# Sheet.net
KiCad netlist of a schematic drawn in Altium Designer
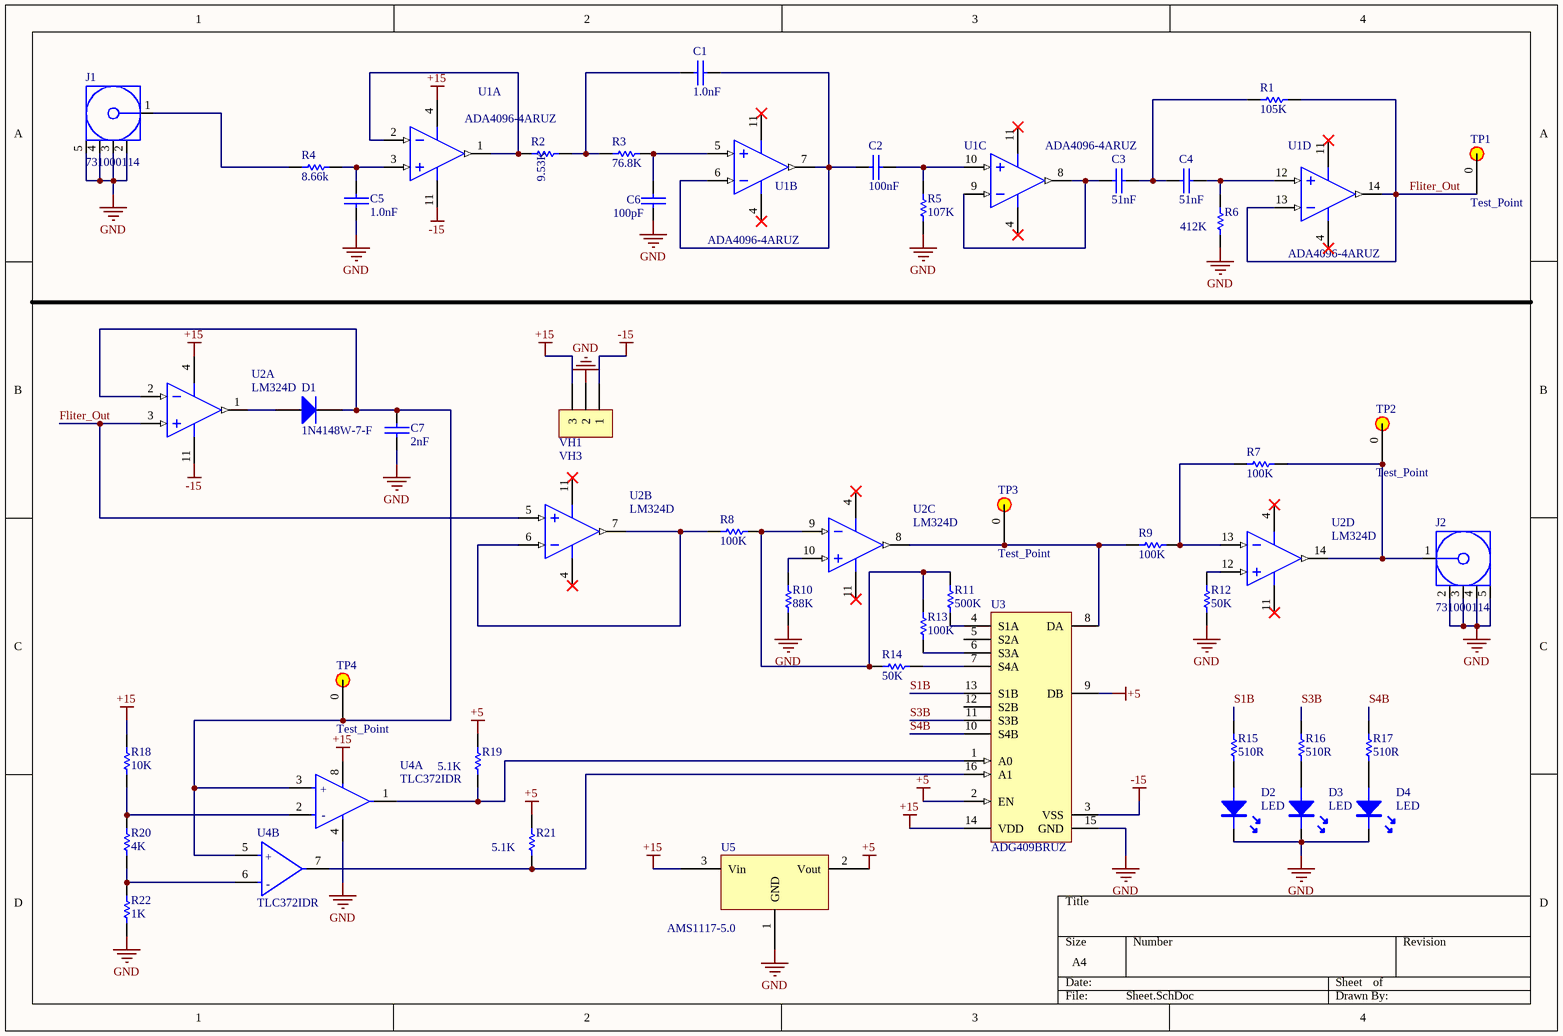
[diagram p0: Sheet.SchDoc]

(export (version "E")
  (design (tool "Eeschema 10.0.6"))
  (components
    (comp (ref "C1")
      (value "1.0nF")
      (footprint "0805C")
      (description "无极性电容")
      (libsource (lib "电容") (part "CAP"))
    )
    (comp (ref "C2")
      (value "100nF")
      (footprint "0805C")
      (description "无极性电容")
      (libsource (lib "电容") (part "CAP"))
    )
    (comp (ref "C3")
      (value "51nF")
      (footprint "0805C")
      (description "无极性电容")
      (libsource (lib "电容") (part "CAP"))
    )
    (comp (ref "C4")
      (value "51nF")
      (footprint "0805C")
      (description "无极性电容")
      (libsource (lib "电容") (part "CAP"))
    )
    (comp (ref "C5")
      (value "1.0nF")
      (footprint "0805C")
      (description "无极性电容")
      (libsource (lib "电容") (part "CAP"))
    )
    (comp (ref "C6")
      (value "100pF")
      (footprint "0805C")
      (description "无极性电容")
      (libsource (lib "电容") (part "CAP"))
    )
    (comp (ref "C7")
      (value "2nF")
      (footprint "0805C")
      (description "无极性电容")
      (libsource (lib "电容") (part "CAP"))
    )
    (comp (ref "D1")
      (value "1N4148W-7-F")
      (footprint "DIOD-SOD123-2_V")
      (description "Fast Switching Diode, 100 V, 0.15 A, -65 to 150 degC, 2-Pin?SOD123, RoHS, Tape and Reel")
      (fields (field (name "MANUFACTURER") "DiodesIncorporated"))
      (libsource (lib "Altium Content Vault") (part "D-AK-2"))
    )
    (comp (ref "D2") (value "LED") (footprint "LED-0805R") (libsource (lib "LED") (part "LED")))
    (comp (ref "D3") (value "LED") (footprint "LED-0805R") (libsource (lib "LED") (part "LED")))
    (comp (ref "D4") (value "LED") (footprint "LED-0805R") (libsource (lib "LED") (part "LED")))
    (comp (ref "J1")
      (value "731000114")
      (footprint "MOLX-731000114_V")
      (description "SMA Right-Angle PCB Jack Receptacle, Brass Body, Gold Plated, 50 Ohm, 5-Pin THD, RoHS, Tray")
      (fields (field (name "MANUFACTURER") "Molex"))
      (libsource (lib "Altium Content Vault") (part "CN-S-4F-RF5"))
    )
    (comp (ref "J2")
      (value "731000114")
      (footprint "MOLX-731000114_V")
      (description "SMA Right-Angle PCB Jack Receptacle, Brass Body, Gold Plated, 50 Ohm, 5-Pin THD, RoHS, Tray")
      (fields (field (name "MANUFACTURER") "Molex"))
      (libsource (lib "Altium Content Vault") (part "CN-S-4F-RF5"))
    )
    (comp (ref "R1") (value "105K") (footprint "0805R") (libsource (lib "电阻") (part "RES")))
    (comp (ref "R2") (value "9.53K") (footprint "0805R") (libsource (lib "电阻") (part "RES")))
    (comp (ref "R3") (value "76.8K") (footprint "0805R") (libsource (lib "电阻") (part "RES")))
    (comp (ref "R4") (value "8.66k") (footprint "0805R") (libsource (lib "电阻") (part "RES")))
    (comp (ref "R5") (value "107K") (footprint "0805R") (libsource (lib "电阻") (part "RES")))
    (comp (ref "R6") (value "412K") (footprint "0805R") (libsource (lib "电阻") (part "RES")))
    (comp (ref "R7") (value "100K") (footprint "0805R") (libsource (lib "电阻") (part "RES")))
    (comp (ref "R8") (value "100K") (footprint "0805R") (libsource (lib "电阻") (part "RES")))
    (comp (ref "R9") (value "100K") (footprint "0805R") (libsource (lib "电阻") (part "RES")))
    (comp (ref "R10") (value "88K") (footprint "0805R") (libsource (lib "电阻") (part "RES")))
    (comp (ref "R11") (value "500K") (footprint "0805R") (libsource (lib "电阻") (part "RES")))
    (comp (ref "R12") (value "50K") (footprint "0805R") (libsource (lib "电阻") (part "RES")))
    (comp (ref "R13") (value "100K") (footprint "0805R") (libsource (lib "电阻") (part "RES")))
    (comp (ref "R14") (value "50K") (footprint "0805R") (libsource (lib "电阻") (part "RES")))
    (comp (ref "R15") (value "510R") (footprint "0805R") (libsource (lib "电阻") (part "RES")))
    (comp (ref "R16") (value "510R") (footprint "0805R") (libsource (lib "电阻") (part "RES")))
    (comp (ref "R17") (value "510R") (footprint "0805R") (libsource (lib "电阻") (part "RES")))
    (comp (ref "R18") (value "10K") (footprint "0805R") (libsource (lib "电阻") (part "RES")))
    (comp (ref "R19") (value "5.1K") (footprint "0805R") (libsource (lib "电阻") (part "RES")))
    (comp (ref "R20") (value "4K") (footprint "0805R") (libsource (lib "电阻") (part "RES")))
    (comp (ref "R21") (value "5.1K") (footprint "0805R") (libsource (lib "电阻") (part "RES")))
    (comp (ref "R22") (value "1K") (footprint "0805R") (libsource (lib "电阻") (part "RES")))
    (comp (ref "TP1")
      (value "Test_Point")
      (footprint "TestPoint FootPrint")
      (libsource (lib "tp") (part "Test_Point"))
    )
    (comp (ref "TP2")
      (value "Test_Point")
      (footprint "TestPoint FootPrint")
      (libsource (lib "tp") (part "Test_Point"))
    )
    (comp (ref "TP3")
      (value "Test_Point")
      (footprint "TestPoint FootPrint")
      (libsource (lib "tp") (part "Test_Point"))
    )
    (comp (ref "TP4")
      (value "Test_Point")
      (footprint "TestPoint FootPrint")
      (libsource (lib "tp") (part "Test_Point"))
    )
    (comp (ref "U1")
      (value "ADA4096-4ARUZ")
      (footprint "ADI-RU-14_L")
      (fields (field (name "MANUFACTURER") "Analog Devices") (field (name "GENERIC PART NUMBER") "ADA4096-4"))
      (libsource (lib "Analog_Devices_ADA4096_4ARUZ") (part "ADA4096-4ARUZ"))
    )
    (comp (ref "U2")
      (value "LM324D")
      (footprint "D0014A_L")
      (fields (field (name "MANUFACTURER") "Texas Instruments"))
      (libsource (lib "Altium Content Vault") (part "TI-LMX24_2902X-X14"))
    )
    (comp (ref "U3")
      (value "ADG409BRUZ")
      (footprint "ADI-RU-16_N")
      (fields (field (name "MANUFACTURER") "Analog Devices"))
      (libsource (lib "Altium Content Vault") (part "ADI-ADG409-RU-16"))
    )
    (comp (ref "U4")
      (value "TLC372IDR")
      (footprint "FP-D0008A-MFG")
      (description "IC DIFF COMP DUAL 8-SOIC")
      (fields
        (field (name "MANUFACTURER") "Texas Instruments")
        (field (name "OCTOPART") "https://octopart.com/tlc372idr-texas+instruments-841294")
      )
      (libsource (lib "Altium Content Vault") (part "c7de155b62542436dacb6ff186a4a6f"))
    )
    (comp (ref "U5")
      (value "AMS1117-5.0")
      (footprint "SOT223")
      (description "三端稳压芯片")
      (libsource (lib "电源芯片") (part "AMS1117"))
    )
    (comp (ref "VH1") (value "VH3") (footprint "VH3.96-3A") (libsource (lib "XH，VH") (part "VH3")))
  )
  (nets
    (net (code "1") (name "+5") (class "Default")
      (node (ref "R19") (pin "2") (pinfunction "2_2") (pintype "passive"))
      (node (ref "R21") (pin "2") (pinfunction "2_2") (pintype "passive"))
      (node (ref "U3") (pin "2") (pinfunction "EN_2") (pintype "input"))
      (node (ref "U3") (pin "9") (pinfunction "DB_9") (pintype "passive"))
      (node (ref "U5") (pin "2") (pinfunction "Vout_2") (pintype "passive"))
    )
    (net (code "2") (name "+15") (class "Default")
      (node (ref "R18") (pin "2") (pinfunction "2_2") (pintype "passive"))
      (node (ref "U1") (pin "4") (pinfunction "+V_4") (pintype "power_in"))
      (node (ref "U2") (pin "4") (pinfunction "VCC_4") (pintype "power_in"))
      (node (ref "U3") (pin "14") (pinfunction "VDD_14") (pintype "power_in"))
      (node (ref "U4") (pin "8") (pinfunction "VCC_8") (pintype "power_in"))
      (node (ref "U5") (pin "3") (pinfunction "Vin_3") (pintype "passive"))
      (node (ref "VH1") (pin "3") (pinfunction "3_3") (pintype "passive"))
    )
    (net (code "3") (name "-15") (class "Default")
      (node (ref "U1") (pin "11") (pinfunction "-V_11") (pintype "power_in"))
      (node (ref "U2") (pin "11") (pinfunction "GND_11") (pintype "power_in"))
      (node (ref "U3") (pin "3") (pinfunction "VSS_3") (pintype "power_in"))
      (node (ref "VH1") (pin "1") (pinfunction "1_1") (pintype "passive"))
    )
    (net (code "4") (name "/Fliter_Out") (class "Default")
      (node (ref "R1") (pin "1") (pinfunction "1_1") (pintype "passive"))
      (node (ref "TP1") (pin "0") (pintype "passive"))
      (node (ref "U1") (pin "13") (pinfunction "-IN_D_13") (pintype "input"))
      (node (ref "U1") (pin "14") (pinfunction "OUT_D_14") (pintype "output"))
      (node (ref "U2") (pin "3") (pinfunction "1IN+_3") (pintype "input"))
      (node (ref "U2") (pin "5") (pinfunction "2IN+_5") (pintype "input"))
    )
    (net (code "5") (name "/S1B") (class "Default")
      (node (ref "R15") (pin "1") (pinfunction "1_1") (pintype "passive"))
      (node (ref "U3") (pin "13") (pinfunction "S1B_13") (pintype "passive"))
    )
    (net (code "6") (name "/S3B") (class "Default")
      (node (ref "R16") (pin "1") (pinfunction "1_1") (pintype "passive"))
      (node (ref "U3") (pin "11") (pinfunction "S3B_11") (pintype "passive"))
    )
    (net (code "7") (name "/S4B") (class "Default")
      (node (ref "R17") (pin "1") (pinfunction "1_1") (pintype "passive"))
      (node (ref "U3") (pin "10") (pinfunction "S4B_10") (pintype "passive"))
    )
    (net (code "8") (name "GND") (class "Default")
      (node (ref "C5") (pin "1") (pinfunction "1_1") (pintype "passive"))
      (node (ref "C6") (pin "1") (pinfunction "1_1") (pintype "passive"))
      (node (ref "C7") (pin "2") (pinfunction "2_2") (pintype "passive"))
      (node (ref "D2") (pin "K") (pinfunction "K_K") (pintype "passive"))
      (node (ref "D3") (pin "K") (pinfunction "K_K") (pintype "passive"))
      (node (ref "D4") (pin "K") (pinfunction "K_K") (pintype "passive"))
      (node (ref "J1") (pin "2") (pinfunction "2_2") (pintype "passive"))
      (node (ref "J1") (pin "3") (pinfunction "3_3") (pintype "passive"))
      (node (ref "J1") (pin "4") (pinfunction "4_4") (pintype "passive"))
      (node (ref "J1") (pin "5") (pinfunction "5_5") (pintype "passive"))
      (node (ref "J2") (pin "2") (pinfunction "2_2") (pintype "passive"))
      (node (ref "J2") (pin "3") (pinfunction "3_3") (pintype "passive"))
      (node (ref "J2") (pin "4") (pinfunction "4_4") (pintype "passive"))
      (node (ref "J2") (pin "5") (pinfunction "5_5") (pintype "passive"))
      (node (ref "R10") (pin "2") (pinfunction "2_2") (pintype "passive"))
      (node (ref "R12") (pin "2") (pinfunction "2_2") (pintype "passive"))
      (node (ref "R22") (pin "1") (pinfunction "1_1") (pintype "passive"))
      (node (ref "R5") (pin "1") (pinfunction "1_1") (pintype "passive"))
      (node (ref "R6") (pin "1") (pinfunction "1_1") (pintype "passive"))
      (node (ref "U3") (pin "15") (pinfunction "GND_15") (pintype "power_in"))
      (node (ref "U4") (pin "4") (pinfunction "GND_4") (pintype "power_in"))
      (node (ref "U5") (pin "1") (pinfunction "GND_1") (pintype "passive"))
      (node (ref "VH1") (pin "2") (pinfunction "2_2") (pintype "passive"))
    )
    (net (code "9") (name "Net-(C1-Pad2)") (class "Default")
      (node (ref "C1") (pin "2") (pinfunction "2_2") (pintype "passive"))
      (node (ref "R2") (pin "2") (pinfunction "2_2") (pintype "passive"))
      (node (ref "R3") (pin "1") (pinfunction "1_1") (pintype "passive"))
    )
    (net (code "10") (name "Net-(C3-Pad1)") (class "Default")
      (node (ref "C3") (pin "1") (pinfunction "1_1") (pintype "passive"))
      (node (ref "C4") (pin "2") (pinfunction "2_2") (pintype "passive"))
      (node (ref "R1") (pin "2") (pinfunction "2_2") (pintype "passive"))
    )
    (net (code "11") (name "Net-(D1-A)") (class "Default")
      (node (ref "D1") (pin "1") (pinfunction "A_1") (pintype "passive"))
      (node (ref "U2") (pin "1") (pinfunction "1OUT_1") (pintype "output"))
    )
    (net (code "12") (name "Net-(D1-K)") (class "Default")
      (node (ref "C7") (pin "1") (pinfunction "1_1") (pintype "passive"))
      (node (ref "D1") (pin "2") (pinfunction "K_2") (pintype "passive"))
      (node (ref "TP4") (pin "0") (pintype "passive"))
      (node (ref "U2") (pin "2") (pinfunction "1IN-_2") (pintype "input"))
      (node (ref "U4") (pin "3") (pinfunction "1IN+_3") (pintype "tri_state"))
      (node (ref "U4") (pin "5") (pinfunction "2IN+_5") (pintype "tri_state"))
    )
    (net (code "13") (name "Net-(D2-PadA)") (class "Default")
      (node (ref "D2") (pin "A") (pinfunction "A_A") (pintype "passive"))
      (node (ref "R15") (pin "2") (pinfunction "2_2") (pintype "passive"))
    )
    (net (code "14") (name "Net-(D3-PadA)") (class "Default")
      (node (ref "D3") (pin "A") (pinfunction "A_A") (pintype "passive"))
      (node (ref "R16") (pin "2") (pinfunction "2_2") (pintype "passive"))
    )
    (net (code "15") (name "Net-(D4-PadA)") (class "Default")
      (node (ref "D4") (pin "A") (pinfunction "A_A") (pintype "passive"))
      (node (ref "R17") (pin "2") (pinfunction "2_2") (pintype "passive"))
    )
    (net (code "16") (name "Net-(J1-Pad1)") (class "Default")
      (node (ref "J1") (pin "1") (pinfunction "1_1") (pintype "passive"))
      (node (ref "R4") (pin "1") (pinfunction "1_1") (pintype "passive"))
    )
    (net (code "17") (name "Net-(U1A-+IN_A)") (class "Default")
      (node (ref "C5") (pin "2") (pinfunction "2_2") (pintype "passive"))
      (node (ref "R4") (pin "2") (pinfunction "2_2") (pintype "passive"))
      (node (ref "U1") (pin "3") (pinfunction "+IN_A_3") (pintype "input"))
    )
    (net (code "18") (name "Net-(U1A--IN_A)") (class "Default")
      (node (ref "R2") (pin "1") (pinfunction "1_1") (pintype "passive"))
      (node (ref "U1") (pin "1") (pinfunction "OUT_A_1") (pintype "output"))
      (node (ref "U1") (pin "2") (pinfunction "-IN_A_2") (pintype "input"))
    )
    (net (code "19") (name "Net-(U1B-+IN_B)") (class "Default")
      (node (ref "C6") (pin "2") (pinfunction "2_2") (pintype "passive"))
      (node (ref "R3") (pin "2") (pinfunction "2_2") (pintype "passive"))
      (node (ref "U1") (pin "5") (pinfunction "+IN_B_5") (pintype "input"))
    )
    (net (code "20") (name "Net-(U1B--IN_B)") (class "Default")
      (node (ref "C1") (pin "1") (pinfunction "1_1") (pintype "passive"))
      (node (ref "C2") (pin "2") (pinfunction "2_2") (pintype "passive"))
      (node (ref "U1") (pin "6") (pinfunction "-IN_B_6") (pintype "input"))
      (node (ref "U1") (pin "7") (pinfunction "OUT_B_7") (pintype "output"))
    )
    (net (code "21") (name "Net-(U1C-+IN_C)") (class "Default")
      (node (ref "C2") (pin "1") (pinfunction "1_1") (pintype "passive"))
      (node (ref "R5") (pin "2") (pinfunction "2_2") (pintype "passive"))
      (node (ref "U1") (pin "10") (pinfunction "+IN_C_10") (pintype "input"))
    )
    (net (code "22") (name "Net-(U1C--IN_C)") (class "Default")
      (node (ref "C3") (pin "2") (pinfunction "2_2") (pintype "passive"))
      (node (ref "U1") (pin "8") (pinfunction "OUT_C_8") (pintype "output"))
      (node (ref "U1") (pin "9") (pinfunction "-IN_C_9") (pintype "input"))
    )
    (net (code "23") (name "Net-(U1D-+IN_D)") (class "Default")
      (node (ref "C4") (pin "1") (pinfunction "1_1") (pintype "passive"))
      (node (ref "R6") (pin "2") (pinfunction "2_2") (pintype "passive"))
      (node (ref "U1") (pin "12") (pinfunction "+IN_D_12") (pintype "input"))
    )
    (net (code "24") (name "Net-(U2B-2IN-)") (class "Default")
      (node (ref "R8") (pin "2") (pinfunction "2_2") (pintype "passive"))
      (node (ref "U2") (pin "6") (pinfunction "2IN-_6") (pintype "input"))
      (node (ref "U2") (pin "7") (pinfunction "2OUT_7") (pintype "output"))
    )
    (net (code "25") (name "Net-(U2C-3IN+)") (class "Default")
      (node (ref "R10") (pin "1") (pinfunction "1_1") (pintype "passive"))
      (node (ref "U2") (pin "10") (pinfunction "3IN+_10") (pintype "input"))
    )
    (net (code "26") (name "Net-(U2C-3IN-)") (class "Default")
      (node (ref "R11") (pin "2") (pinfunction "2_2") (pintype "passive"))
      (node (ref "R13") (pin "2") (pinfunction "2_2") (pintype "passive"))
      (node (ref "R14") (pin "2") (pinfunction "2_2") (pintype "passive"))
      (node (ref "R8") (pin "1") (pinfunction "1_1") (pintype "passive"))
      (node (ref "U2") (pin "9") (pinfunction "3IN-_9") (pintype "input"))
    )
    (net (code "27") (name "Net-(U2C-3OUT)") (class "Default")
      (node (ref "R9") (pin "2") (pinfunction "2_2") (pintype "passive"))
      (node (ref "TP3") (pin "0") (pintype "passive"))
      (node (ref "U2") (pin "8") (pinfunction "3OUT_8") (pintype "output"))
      (node (ref "U3") (pin "8") (pinfunction "DA_8") (pintype "passive"))
    )
    (net (code "28") (name "Net-(U2D-4IN+)") (class "Default")
      (node (ref "R12") (pin "1") (pinfunction "1_1") (pintype "passive"))
      (node (ref "U2") (pin "12") (pinfunction "4IN+_12") (pintype "input"))
    )
    (net (code "29") (name "Net-(U2D-4IN-)") (class "Default")
      (node (ref "R7") (pin "2") (pinfunction "2_2") (pintype "passive"))
      (node (ref "R9") (pin "1") (pinfunction "1_1") (pintype "passive"))
      (node (ref "U2") (pin "13") (pinfunction "4IN-_13") (pintype "input"))
    )
    (net (code "30") (name "Net-(U2D-4OUT)") (class "Default")
      (node (ref "J2") (pin "1") (pinfunction "1_1") (pintype "passive"))
      (node (ref "R7") (pin "1") (pinfunction "1_1") (pintype "passive"))
      (node (ref "TP2") (pin "0") (pintype "passive"))
      (node (ref "U2") (pin "14") (pinfunction "4OUT_14") (pintype "output"))
    )
    (net (code "31") (name "Net-(U3-A0)") (class "Default")
      (node (ref "R19") (pin "1") (pinfunction "1_1") (pintype "passive"))
      (node (ref "U3") (pin "1") (pinfunction "A0_1") (pintype "input"))
      (node (ref "U4") (pin "1") (pinfunction "1OUT_1") (pintype "passive"))
    )
    (net (code "32") (name "Net-(U3-A1)") (class "Default")
      (node (ref "R21") (pin "1") (pinfunction "1_1") (pintype "passive"))
      (node (ref "U3") (pin "16") (pinfunction "A1_16") (pintype "input"))
      (node (ref "U4") (pin "7") (pinfunction "2OUT_7") (pintype "passive"))
    )
    (net (code "33") (name "Net-(U3-S1A)") (class "Default")
      (node (ref "R11") (pin "1") (pinfunction "1_1") (pintype "passive"))
      (node (ref "U3") (pin "4") (pinfunction "S1A_4") (pintype "passive"))
    )
    (net (code "34") (name "Net-(U3-S3A)") (class "Default")
      (node (ref "R13") (pin "1") (pinfunction "1_1") (pintype "passive"))
      (node (ref "U3") (pin "6") (pinfunction "S3A_6") (pintype "passive"))
    )
    (net (code "35") (name "Net-(U3-S4A)") (class "Default")
      (node (ref "R14") (pin "1") (pinfunction "1_1") (pintype "passive"))
      (node (ref "U3") (pin "7") (pinfunction "S4A_7") (pintype "passive"))
    )
    (net (code "36") (name "Net-(U4A-1IN-)") (class "Default")
      (node (ref "R18") (pin "1") (pinfunction "1_1") (pintype "passive"))
      (node (ref "R20") (pin "2") (pinfunction "2_2") (pintype "passive"))
      (node (ref "U4") (pin "2") (pinfunction "1IN-_2") (pintype "tri_state"))
    )
    (net (code "37") (name "Net-(U4B-2IN-)") (class "Default")
      (node (ref "R20") (pin "1") (pinfunction "1_1") (pintype "passive"))
      (node (ref "R22") (pin "2") (pinfunction "2_2") (pintype "passive"))
      (node (ref "U4") (pin "6") (pinfunction "2IN-_6") (pintype "tri_state"))
    )
    (net (code "38") (name "unconnected-(U1B-+V-Pad4)") (class "Default")
      (node (ref "U1") (pin "4") (pinfunction "+V_4") (pintype "power_in+no_connect"))
    )
    (net (code "39") (name "unconnected-(U1B--V-Pad11)") (class "Default")
      (node (ref "U1") (pin "11") (pinfunction "-V_11") (pintype "power_in+no_connect"))
    )
    (net (code "40") (name "unconnected-(U1C-+V-Pad4)") (class "Default")
      (node (ref "U1") (pin "4") (pinfunction "+V_4") (pintype "power_in+no_connect"))
    )
    (net (code "41") (name "unconnected-(U1C--V-Pad11)") (class "Default")
      (node (ref "U1") (pin "11") (pinfunction "-V_11") (pintype "power_in+no_connect"))
    )
    (net (code "42") (name "unconnected-(U1D-+V-Pad4)") (class "Default")
      (node (ref "U1") (pin "4") (pinfunction "+V_4") (pintype "power_in+no_connect"))
    )
    (net (code "43") (name "unconnected-(U1D--V-Pad11)") (class "Default")
      (node (ref "U1") (pin "11") (pinfunction "-V_11") (pintype "power_in+no_connect"))
    )
    (net (code "44") (name "unconnected-(U2B-GND-Pad11)") (class "Default")
      (node (ref "U2") (pin "11") (pinfunction "GND_11") (pintype "power_in+no_connect"))
    )
    (net (code "45") (name "unconnected-(U2B-VCC-Pad4)") (class "Default")
      (node (ref "U2") (pin "4") (pinfunction "VCC_4") (pintype "power_in+no_connect"))
    )
    (net (code "46") (name "unconnected-(U2C-GND-Pad11)") (class "Default")
      (node (ref "U2") (pin "11") (pinfunction "GND_11") (pintype "power_in+no_connect"))
    )
    (net (code "47") (name "unconnected-(U2C-VCC-Pad4)") (class "Default")
      (node (ref "U2") (pin "4") (pinfunction "VCC_4") (pintype "power_in+no_connect"))
    )
    (net (code "48") (name "unconnected-(U2D-GND-Pad11)") (class "Default")
      (node (ref "U2") (pin "11") (pinfunction "GND_11") (pintype "power_in+no_connect"))
    )
    (net (code "49") (name "unconnected-(U2D-VCC-Pad4)") (class "Default")
      (node (ref "U2") (pin "4") (pinfunction "VCC_4") (pintype "power_in+no_connect"))
    )
    (net (code "50") (name "unconnected-(U3-S2A-Pad5)") (class "Default")
      (node (ref "U3") (pin "5") (pinfunction "S2A_5") (pintype "passive"))
    )
    (net (code "51") (name "unconnected-(U3-S2B-Pad12)") (class "Default")
      (node (ref "U3") (pin "12") (pinfunction "S2B_12") (pintype "passive"))
    )
  )
)
